# CCU_Sheet.net
KiCad netlist of a schematic drawn in Altium Designer
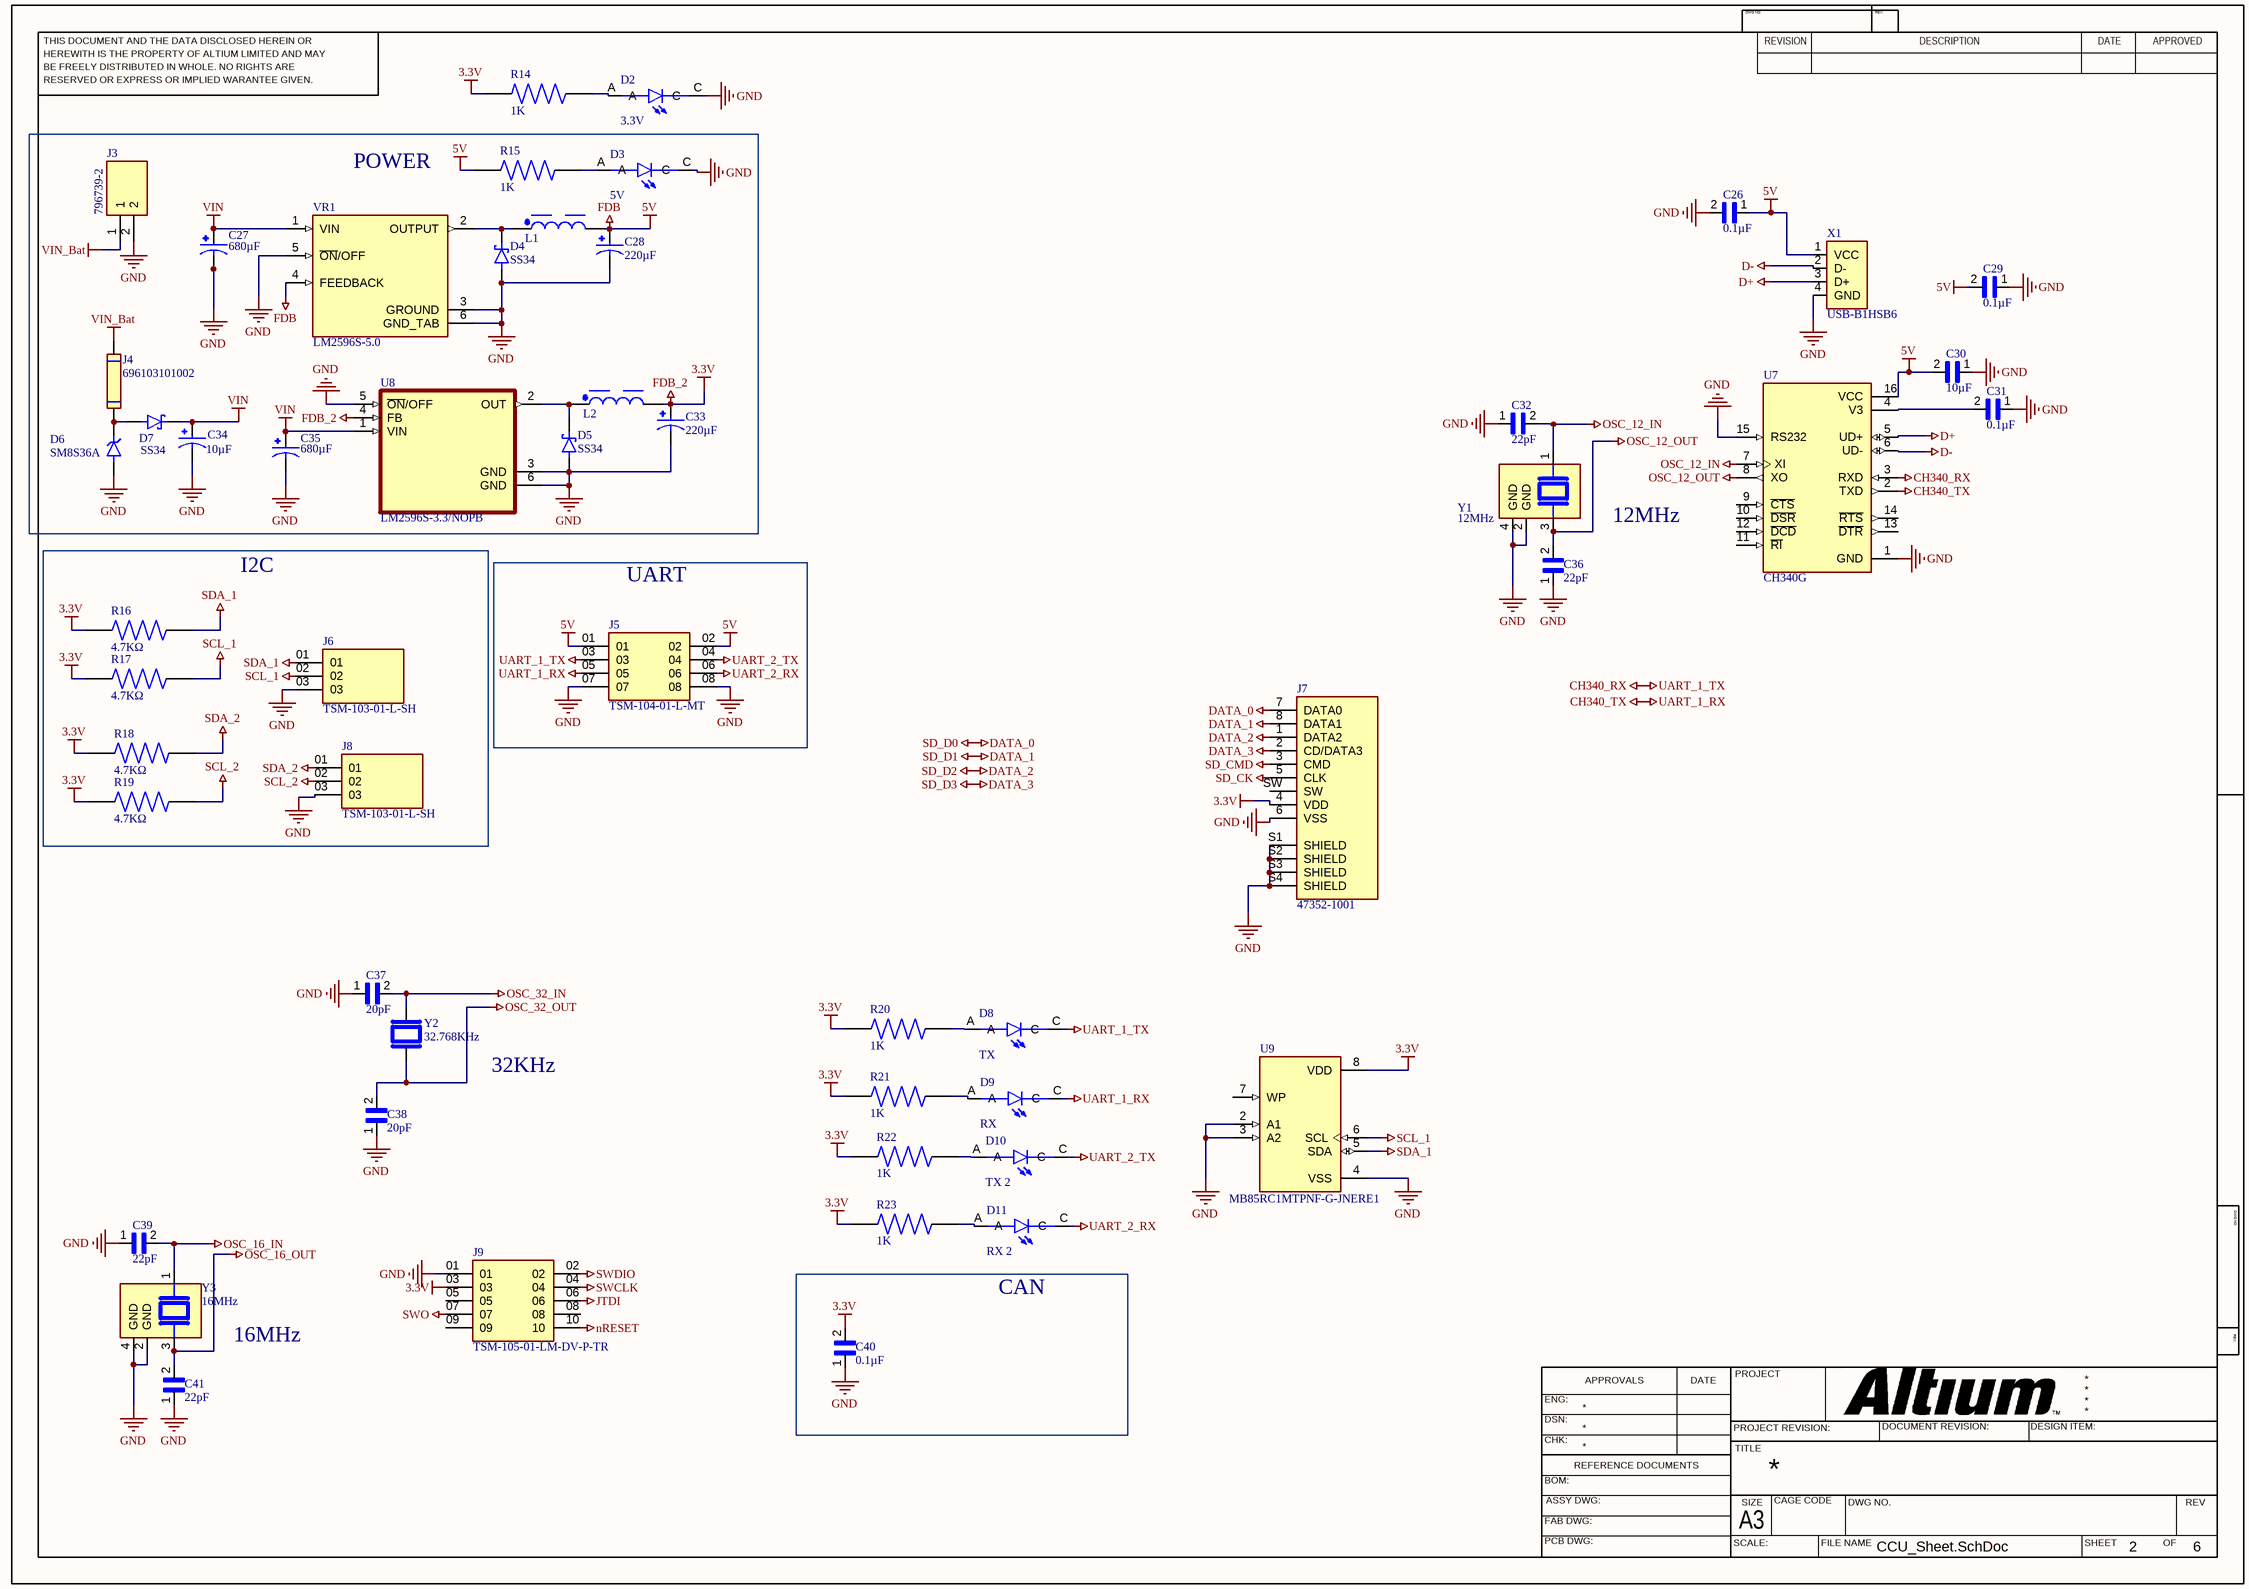
[diagram p0: CCU_Sheet.SchDoc]

(export (version "E")
  (design (tool "Eeschema 10.0.6"))
  (components
    (comp (ref "C26")
      (value "0.1µF")
      (footprint "CAPC1608X90N")
      (description "Multilayer Ceramic Capacitors MLCC - SMD/SMT")
      (fields (field (name "MP") "06035C104MAZ2A"))
      (libsource (lib "06035C104MAZ2A") (part "06035C104MAZ2A"))
    )
    (comp (ref "C27")
      (value "680µF")
      (footprint "CAP_EEEFN1E681UV")
      (description "CAP ALUM 680UF 20% 25V SMD")
      (fields (field (name "MF") "Panasonic Electronic Components") (field (name "MP") "EEE-FN1E681UV"))
      (libsource (lib "EEEFN1E681UV") (part "EEEFN1E681UV"))
    )
    (comp (ref "C28")
      (value "220µF")
      (footprint "CAP_EEEFP1V221AV")
      (description "CAP ALUM 220UF 20% 35V SMD")
      (fields (field (name "MF") "Panasonic Electronic Components") (field (name "MP") "EEE-FP1V221AV"))
      (libsource (lib "") (part "EEEFP1V221AV_1"))
    )
    (comp (ref "C29")
      (value "0.1µF")
      (footprint "CAPC1608X90N")
      (description "Multilayer Ceramic Capacitors MLCC - SMD/SMT")
      (fields (field (name "MP") "06035C104MAZ2A"))
      (libsource (lib "06035C104MAZ2A") (part "06035C104MAZ2A"))
    )
    (comp (ref "C30")
      (value "10µF")
      (footprint "CAPC1608X90N")
      (description "Multilayer Ceramic Capacitors MLCC - SMD/SMT")
      (fields (field (name "MP") "06035C104MAZ2A"))
      (libsource (lib "06035C104MAZ2A") (part "06035C104MAZ2A"))
    )
    (comp (ref "C31")
      (value "0.1µF")
      (footprint "CAPC1608X90N")
      (description "Multilayer Ceramic Capacitors MLCC - SMD/SMT")
      (fields (field (name "MP") "06035C104MAZ2A"))
      (libsource (lib "06035C104MAZ2A") (part "06035C104MAZ2A"))
    )
    (comp (ref "C32")
      (value "22pF")
      (footprint "CAPC1005X61N")
      (fields (field (name "MP") "VJ0402D200FXAAJ"))
      (libsource (lib "VJ0402D200FXAAJ") (part "VJ0402D200FXAAJ"))
    )
    (comp (ref "C33")
      (value "220µF")
      (footprint "CAP_EEEFP1V221AV")
      (description "CAP ALUM 220UF 20% 35V SMD")
      (fields (field (name "MF") "Panasonic Electronic Components") (field (name "MP") "EEE-FP1V221AV"))
      (libsource (lib "EEEFP1V221AV") (part "EEEFP1V221AV"))
    )
    (comp (ref "C34")
      (value "10µF")
      (footprint "CAPPRD500W50D500H1100")
      (description "10ÂµF 25V Aluminum Electrolytic Capacitors Radial, Can 2000 Hrs @ 85Â°C")
      (fields (field (name "MF") "Panasonic") (field (name "MP") "ECEA1EN100UB"))
      (libsource (lib "ECEA1EN100UB") (part "ECEA1EN100UB"))
    )
    (comp (ref "C35")
      (value "680µF")
      (footprint "CAP_EEEFN1E681UV")
      (description "CAP ALUM 680UF 20% 25V SMD")
      (fields (field (name "MF") "Panasonic Electronic Components") (field (name "MP") "EEE-FN1E681UV"))
      (libsource (lib "") (part "EEEFN1E681UV_1"))
    )
    (comp (ref "C36")
      (value "22pF")
      (footprint "CAPC1005X61N")
      (fields (field (name "MP") "VJ0402D200FXAAJ"))
      (libsource (lib "") (part "VJ0402D200FXAAJ_1"))
    )
    (comp (ref "C37")
      (value "20pF")
      (footprint "CAPC1005X61N")
      (fields (field (name "MP") "VJ0402D200FXAAJ"))
      (libsource (lib "VJ0402D200FXAAJ") (part "VJ0402D200FXAAJ"))
    )
    (comp (ref "C38")
      (value "20pF")
      (footprint "CAPC1005X61N")
      (fields (field (name "MP") "VJ0402D200FXAAJ"))
      (libsource (lib "") (part "VJ0402D200FXAAJ_1"))
    )
    (comp (ref "C39")
      (value "22pF")
      (footprint "CAPC1005X61N")
      (fields (field (name "MP") "VJ0402D200FXAAJ"))
      (libsource (lib "VJ0402D200FXAAJ") (part "VJ0402D200FXAAJ"))
    )
    (comp (ref "C40")
      (value "0.1µF")
      (footprint "CAPC1608X90N")
      (description "Multilayer Ceramic Capacitors MLCC - SMD/SMT")
      (fields (field (name "MP") "06035C104MAZ2A"))
      (libsource (lib "") (part "06035C104MAZ2A_1"))
    )
    (comp (ref "C41")
      (value "22pF")
      (footprint "CAPC1005X61N")
      (fields (field (name "MP") "VJ0402D200FXAAJ"))
      (libsource (lib "") (part "VJ0402D200FXAAJ_1"))
    )
    (comp (ref "D2")
      (value "3.3V")
      (footprint "LEDC2012X70N")
      (description "LED Uni-Color Green 4-Pin Chip 0805 T/R")
      (fields (field (name "MP") "597-3305-607F"))
      (libsource (lib "597-3305-607F") (part "597-3305-607F"))
    )
    (comp (ref "D3")
      (value "5V")
      (footprint "LEDC2012X70N")
      (description "LED Uni-Color Green 4-Pin Chip 0805 T/R")
      (fields (field (name "MP") "597-3305-607F"))
      (libsource (lib "597-3305-607F") (part "597-3305-607F"))
    )
    (comp (ref "D4")
      (value "SS34")
      (footprint "DIO_SS34")
      (description "3A, 40V, Schottky Rectifier")
      (fields (field (name "MF") "Taiwan Semiconductor"))
      (libsource (lib "SS34") (part "SS34"))
    )
    (comp (ref "D5")
      (value "SS34")
      (footprint "DIO_SS34")
      (description "3A, 40V, Schottky Rectifier")
      (fields (field (name "MF") "Taiwan Semiconductor"))
      (libsource (lib "SS34") (part "SS34"))
    )
    (comp (ref "D6")
      (value "SM8S36A")
      (footprint "TVSP_SM8S36A")
      (libsource (lib "SM8S36A") (part "SM8S36A"))
    )
    (comp (ref "D7")
      (value "SS34")
      (footprint "DIO_SS34")
      (description "3A, 40V, Schottky Rectifier")
      (fields (field (name "MF") "Taiwan Semiconductor"))
      (libsource (lib "SS34") (part "SS34"))
    )
    (comp (ref "D8")
      (value "TX")
      (footprint "LEDC2012X70N")
      (description "LED Uni-Color Green 4-Pin Chip 0805 T/R")
      (fields (field (name "MP") "597-3305-607F"))
      (libsource (lib "597-3305-607F") (part "597-3305-607F"))
    )
    (comp (ref "D9")
      (value "RX")
      (footprint "LEDC2012X70N")
      (description "LED Uni-Color Green 4-Pin Chip 0805 T/R")
      (fields (field (name "MP") "597-3305-607F"))
      (libsource (lib "597-3305-607F") (part "597-3305-607F"))
    )
    (comp (ref "D10")
      (value "TX 2")
      (footprint "LEDC2012X70N")
      (description "LED Uni-Color Green 4-Pin Chip 0805 T/R")
      (fields (field (name "MP") "597-3305-607F"))
      (libsource (lib "597-3305-607F") (part "597-3305-607F"))
    )
    (comp (ref "D11")
      (value "RX 2")
      (footprint "LEDC2012X70N")
      (description "LED Uni-Color Green 4-Pin Chip 0805 T/R")
      (fields (field (name "MP") "597-3305-607F"))
      (libsource (lib "597-3305-607F") (part "597-3305-607F"))
    )
    (comp (ref "J3")
      (value "796739-2")
      (footprint "TE_796739-2")
      (description "Conn Terminal Block F 2 POS 9.53mm Solder RA Thru-Hole 32A/Contact")
      (fields (field (name "MF") "TE Connectivity"))
      (libsource (lib "796739-2") (part "796739-2"))
    )
    (comp (ref "J4")
      (value "696103101002")
      (footprint "696103101002")
      (fields (field (name "MF") "{'manufacturer': u'~{W}xfcrth Elektronik'}"))
      (libsource (lib "696103101002") (part "696103101002"))
    )
    (comp (ref "J5")
      (value "TSM-104-01-L-MT")
      (footprint "SAMTEC_TSM-104-01-L-MT")
      (description "TSM Series .100 Surface Mount Terminal Strip")
      (fields (field (name "MF") "Samtec"))
      (libsource (lib "TSM-104-01-L-MT") (part "TSM-104-01-L-MT"))
    )
    (comp (ref "J6")
      (value "TSM-103-01-L-SH")
      (footprint "SAMTEC_TSM-103-01-L-SH")
      (fields (field (name "MF") "Samtec Inc."))
      (libsource (lib "TSM-103-01-L-SH (1)") (part "TSM-103-01-L-SH"))
    )
    (comp (ref "J7")
      (value "47352-1001")
      (footprint "MOLEX_47352-1001")
      (description "8 (6 + 2) Position Card Connector Secure Digital - microSDâ„¢ Surface Mount, Right Angle Gold")
      (fields (field (name "MP") "473521001") (field (name "MF") "Molex"))
      (libsource (lib "47352-1001") (part "47352-1001"))
    )
    (comp (ref "J8")
      (value "TSM-103-01-L-SH")
      (footprint "SAMTEC_TSM-103-01-L-SH")
      (fields (field (name "MF") "Samtec Inc."))
      (libsource (lib "TSM-103-01-L-SH (1)") (part "TSM-103-01-L-SH"))
    )
    (comp (ref "J9")
      (value "TSM-105-01-LM-DV-P-TR")
      (footprint "SAMTEC_TSM-105-01-LM-DV-P-TR")
      (description "TSM - Samtec 2.54mm Dual Row Vertical Surface Mount Header 5.84mm Post Height (01) - Fast Stock")
      (fields (field (name "MF") "Samtec"))
      (libsource (lib "TSM-105-01-LM-DV-P-TR") (part "TSM-105-01-LM-DV-P-TR"))
    )
    (comp (ref "L1")
      (value "33uH, 4.2A")
      (footprint "WE-PD_1210")
      (description "WE-PD SMT Power Inductor, size 1210, 33uH, 4.2A, 45mOhm")
      (fields
        (field (name "MANUFACTURER PART NUMBER") "7447709330")
        (field (name "MANUFACTURER") "Wurth Elektronik")
      )
      (libsource (lib "Altium_WE-PD_rev22g") (part "7447709330"))
    )
    (comp (ref "L2")
      (value "33uH, 4.2A")
      (footprint "WE-PD_1210")
      (description "WE-PD SMT Power Inductor, size 1210, 33uH, 4.2A, 45mOhm")
      (fields
        (field (name "MANUFACTURER PART NUMBER") "7447709330")
        (field (name "MANUFACTURER") "Wurth Elektronik")
      )
      (libsource (lib "Altium_WE-PD_rev22g") (part "7447709330"))
    )
    (comp (ref "R14")
      (value "1K")
      (footprint "RESC3116X65N")
      (fields (field (name "MF") "Yageo Corporation") (field (name "MP") "RC1206JR071KL"))
      (libsource (lib "RC1206JR-071KL") (part "RC1206JR-071KL"))
    )
    (comp (ref "R15")
      (value "1K")
      (footprint "RESC3116X65N")
      (fields (field (name "MF") "Yageo Corporation") (field (name "MP") "RC1206JR071KL"))
      (libsource (lib "RC1206JR-071KL") (part "RC1206JR-071KL"))
    )
    (comp (ref "R16")
      (value "4.7KΩ")
      (footprint "RES_ERJS06J472V")
      (fields (field (name "MP") "ERJS06J472V"))
      (libsource (lib "ERJS06J472V") (part "ERJS06J472V"))
    )
    (comp (ref "R17")
      (value "4.7KΩ")
      (footprint "RES_ERJS06J472V")
      (fields (field (name "MP") "ERJS06J472V"))
      (libsource (lib "ERJS06J472V") (part "ERJS06J472V"))
    )
    (comp (ref "R18")
      (value "4.7KΩ")
      (footprint "RES_ERJS06J472V")
      (fields (field (name "MP") "ERJS06J472V"))
      (libsource (lib "ERJS06J472V") (part "ERJS06J472V"))
    )
    (comp (ref "R19")
      (value "4.7KΩ")
      (footprint "RES_ERJS06J472V")
      (fields (field (name "MP") "ERJS06J472V"))
      (libsource (lib "ERJS06J472V") (part "ERJS06J472V"))
    )
    (comp (ref "R20")
      (value "1K")
      (footprint "RESC3116X65N")
      (fields (field (name "MF") "Yageo Corporation") (field (name "MP") "RC1206JR071KL"))
      (libsource (lib "RC1206JR-071KL") (part "RC1206JR-071KL"))
    )
    (comp (ref "R21")
      (value "1K")
      (footprint "RESC3116X65N")
      (fields (field (name "MF") "Yageo Corporation") (field (name "MP") "RC1206JR071KL"))
      (libsource (lib "RC1206JR-071KL") (part "RC1206JR-071KL"))
    )
    (comp (ref "R22")
      (value "1K")
      (footprint "RESC3116X65N")
      (fields (field (name "MF") "Yageo Corporation") (field (name "MP") "RC1206JR071KL"))
      (libsource (lib "RC1206JR-071KL") (part "RC1206JR-071KL"))
    )
    (comp (ref "R23")
      (value "1K")
      (footprint "RESC3116X65N")
      (fields (field (name "MF") "Yageo Corporation") (field (name "MP") "RC1206JR071KL"))
      (libsource (lib "RC1206JR-071KL") (part "RC1206JR-071KL"))
    )
    (comp (ref "U7")
      (value "CH340G")
      (footprint "SOIC127P600X180-16N")
      (description "USB Interface Integrated Circuit")
      (fields (field (name "MP") "Ch340G") (field (name "MF") "WCH"))
      (libsource (lib "CH340G") (part "CH340G"))
    )
    (comp (ref "U8")
      (value "LM2596S-3.3/NOPB")
      (footprint "VREG_LM2596S-3.3/NOPB")
      (libsource (lib "LM2596S-3.3_NOPB") (part "LM2596S-3.3/NOPB"))
    )
    (comp (ref "U9")
      (value "MB85RC1MTPNF-G-JNERE1")
      (footprint "SOIC127P600X175-8N")
      (description "FRAM _Ferroelectric RAM_ Memory IC 1Mb _128K x 8_ IÂ²C 3.4MHz 130ns 8-SOP")
      (fields (field (name "MF") "Fujitsu Electronics"))
      (libsource (lib "MB85RC1MTPNF-G-JNERE1") (part "MB85RC1MTPNF-G-JNERE1"))
    )
    (comp (ref "VR1")
      (value "LM2596S-5.0")
      (footprint "TO170P1524X483-6N")
      (description "SIMPLE SWITCHER&reg; 4.5V to 40V, 3A Low Component Count Step-Down Regulator")
      (fields (field (name "MP") "LM2596S-5.0/NOPB") (field (name "MF") "Texas Instruments"))
      (libsource (lib "LM2596S-5.0") (part "LM2596S-5.0"))
    )
    (comp (ref "X1")
      (value "USB-B1HSB6")
      (footprint "OST_USB-B1HSB6")
      (description "USB-B (USB TYPE-B) - Receptacle Connector 4 Position Through Hole, Right Angle")
      (fields (field (name "MF") "On Shore"))
      (libsource (lib "USB-B1HSB6") (part "USB-B1HSB6"))
    )
    (comp (ref "Y1")
      (value "12MHz")
      (footprint "XTAL_7M25090002")
      (description "16 MHz Â±10ppm Crystal 18pF 4-SMD, No Lead")
      (fields (field (name "MF") "TXC") (field (name "MP") "7M25090002"))
      (libsource (lib "7M25090002") (part "7M25090002"))
    )
    (comp (ref "Y2")
      (value "32.768KHz")
      (footprint "XTAL_ABS06-32.768KHZ-9-1-T")
      (description "32.768 kHz Â±10ppm Crystal 9pF 90 kOhms 2-SMD, No Lead")
      (fields (field (name "MF") "Abracon") (field (name "MP") "ABS06-32.768KHZ-9-1-T"))
      (libsource (lib "ABS06-32.768KHZ-9-1-T") (part "ABS06-32.768KHZ-9-1-T"))
    )
    (comp (ref "Y3")
      (value "16MHz")
      (footprint "XTAL_7M25090002")
      (description "25 MHz Â±10ppm Crystal 18pF 4-SMD, No Lead")
      (fields (field (name "MF") "TXC") (field (name "MP") "7M25090002"))
      (libsource (lib "7M25090002") (part "7M25090002"))
    )
  )
  (nets
    (net (code "1") (name "3.3V") (class "Default")
      (node (ref "C33") (pin "1") (pinfunction "1_1") (pintype "passive"))
      (node (ref "C40") (pin "2") (pinfunction "2_2") (pintype "passive"))
      (node (ref "J7") (pin "4") (pinfunction "VDD_4") (pintype "passive"))
      (node (ref "J9") (pin "03") (pinfunction "03_03") (pintype "passive"))
      (node (ref "L2") (pin "2") (pinfunction "2_2") (pintype "passive"))
      (node (ref "R14") (pin "1") (pinfunction "1_1") (pintype "passive"))
      (node (ref "R16") (pin "2") (pinfunction "2_2") (pintype "passive"))
      (node (ref "R17") (pin "1") (pinfunction "1_1") (pintype "passive"))
      (node (ref "R18") (pin "2") (pinfunction "2_2") (pintype "passive"))
      (node (ref "R19") (pin "1") (pinfunction "1_1") (pintype "passive"))
      (node (ref "R20") (pin "1") (pinfunction "1_1") (pintype "passive"))
      (node (ref "R21") (pin "1") (pinfunction "1_1") (pintype "passive"))
      (node (ref "R22") (pin "1") (pinfunction "1_1") (pintype "passive"))
      (node (ref "R23") (pin "1") (pinfunction "1_1") (pintype "passive"))
      (node (ref "U8") (pin "4") (pinfunction "FB_4") (pintype "input"))
      (node (ref "U9") (pin "8") (pinfunction "VDD_8") (pintype "power_in"))
    )
    (net (code "2") (name "5V") (class "Default")
      (node (ref "C26") (pin "1") (pinfunction "1_1") (pintype "passive"))
      (node (ref "C28") (pin "1") (pinfunction "1_1") (pintype "passive"))
      (node (ref "C29") (pin "2") (pinfunction "2_2") (pintype "passive"))
      (node (ref "C30") (pin "2") (pinfunction "2_2") (pintype "passive"))
      (node (ref "J5") (pin "01") (pinfunction "01_01") (pintype "passive"))
      (node (ref "J5") (pin "02") (pinfunction "02_02") (pintype "passive"))
      (node (ref "L1") (pin "2") (pinfunction "2_2") (pintype "passive"))
      (node (ref "R15") (pin "1") (pinfunction "1_1") (pintype "passive"))
      (node (ref "U7") (pin "16") (pinfunction "VCC_16") (pintype "power_in"))
      (node (ref "VR1") (pin "4") (pinfunction "FEEDBACK_4") (pintype "input"))
      (node (ref "X1") (pin "1") (pinfunction "VCC_1") (pintype "power_in"))
    )
    (net (code "3") (name "CH340_RX") (class "Default")
      (node (ref "D8") (pin "C") (pinfunction "C_C") (pintype "passive"))
      (node (ref "J5") (pin "03") (pinfunction "03_03") (pintype "passive"))
      (node (ref "U7") (pin "3") (pinfunction "RXD_3") (pintype "input"))
    )
    (net (code "4") (name "CH340_TX") (class "Default")
      (node (ref "D9") (pin "C") (pinfunction "C_C") (pintype "passive"))
      (node (ref "J5") (pin "05") (pinfunction "05_05") (pintype "passive"))
      (node (ref "U7") (pin "2") (pinfunction "TXD_2") (pintype "output"))
    )
    (net (code "5") (name "D+") (class "Default")
      (node (ref "U7") (pin "5") (pinfunction "UD+_5") (pintype "bidirectional"))
      (node (ref "X1") (pin "3") (pinfunction "D+_3") (pintype "bidirectional"))
    )
    (net (code "6") (name "D-") (class "Default")
      (node (ref "U7") (pin "6") (pinfunction "UD-_6") (pintype "bidirectional"))
      (node (ref "X1") (pin "2") (pinfunction "D-_2") (pintype "bidirectional"))
    )
    (net (code "7") (name "DATA_0") (class "Default")
      (node (ref "J7") (pin "7") (pinfunction "DATA0_7") (pintype "passive"))
    )
    (net (code "8") (name "DATA_1") (class "Default")
      (node (ref "J7") (pin "8") (pinfunction "DATA1_8") (pintype "passive"))
    )
    (net (code "9") (name "DATA_2") (class "Default")
      (node (ref "J7") (pin "1") (pinfunction "DATA2_1") (pintype "passive"))
    )
    (net (code "10") (name "DATA_3") (class "Default")
      (node (ref "J7") (pin "2") (pinfunction "CD/DATA3_2") (pintype "passive"))
    )
    (net (code "11") (name "GND") (class "Default")
      (node (ref "C26") (pin "2") (pinfunction "2_2") (pintype "passive"))
      (node (ref "C27") (pin "2") (pinfunction "2_2") (pintype "passive"))
      (node (ref "C28") (pin "2") (pinfunction "2_2") (pintype "passive"))
      (node (ref "C29") (pin "1") (pinfunction "1_1") (pintype "passive"))
      (node (ref "C30") (pin "1") (pinfunction "1_1") (pintype "passive"))
      (node (ref "C31") (pin "1") (pinfunction "1_1") (pintype "passive"))
      (node (ref "C32") (pin "1") (pinfunction "1_1") (pintype "passive"))
      (node (ref "C33") (pin "2") (pinfunction "2_2") (pintype "passive"))
      (node (ref "C34") (pin "N") (pinfunction "N_N") (pintype "passive"))
      (node (ref "C35") (pin "2") (pinfunction "2_2") (pintype "passive"))
      (node (ref "C36") (pin "1") (pinfunction "1_1") (pintype "passive"))
      (node (ref "C37") (pin "1") (pinfunction "1_1") (pintype "passive"))
      (node (ref "C38") (pin "1") (pinfunction "1_1") (pintype "passive"))
      (node (ref "C39") (pin "1") (pinfunction "1_1") (pintype "passive"))
      (node (ref "C40") (pin "1") (pinfunction "1_1") (pintype "passive"))
      (node (ref "C41") (pin "1") (pinfunction "1_1") (pintype "passive"))
      (node (ref "D2") (pin "C") (pinfunction "C_C") (pintype "passive"))
      (node (ref "D3") (pin "C") (pinfunction "C_C") (pintype "passive"))
      (node (ref "D4") (pin "A") (pinfunction "A_A") (pintype "passive"))
      (node (ref "D5") (pin "A") (pinfunction "A_A") (pintype "passive"))
      (node (ref "D6") (pin "2") (pinfunction "A_2") (pintype "passive"))
      (node (ref "J3") (pin "2") (pinfunction "2_2") (pintype "passive"))
      (node (ref "J5") (pin "07") (pinfunction "07_07") (pintype "passive"))
      (node (ref "J5") (pin "08") (pinfunction "08_08") (pintype "passive"))
      (node (ref "J6") (pin "03") (pinfunction "03_03") (pintype "passive"))
      (node (ref "J7") (pin "6") (pinfunction "VSS_6") (pintype "passive"))
      (node (ref "J7") (pin "S1") (pinfunction "SHIELD_S1") (pintype "passive"))
      (node (ref "J7") (pin "S2") (pinfunction "SHIELD_S2") (pintype "passive"))
      (node (ref "J7") (pin "S3") (pinfunction "SHIELD_S3") (pintype "passive"))
      (node (ref "J7") (pin "S4") (pinfunction "SHIELD_S4") (pintype "passive"))
      (node (ref "J8") (pin "03") (pinfunction "03_03") (pintype "passive"))
      (node (ref "J9") (pin "01") (pinfunction "01_01") (pintype "passive"))
      (node (ref "U7") (pin "1") (pinfunction "GND_1") (pintype "power_in"))
      (node (ref "U7") (pin "15") (pinfunction "RS232_15") (pintype "input"))
      (node (ref "U8") (pin "3") (pinfunction "GND_3") (pintype "power_in"))
      (node (ref "U8") (pin "5") (pinfunction "~{ON}/OFF_5") (pintype "input"))
      (node (ref "U8") (pin "6") (pinfunction "GND_6") (pintype "power_in"))
      (node (ref "U9") (pin "2") (pinfunction "A1_2") (pintype "input"))
      (node (ref "U9") (pin "3") (pinfunction "A2_3") (pintype "input"))
      (node (ref "U9") (pin "4") (pinfunction "VSS_4") (pintype "power_in"))
      (node (ref "VR1") (pin "3") (pinfunction "GROUND_3") (pintype "power_in"))
      (node (ref "VR1") (pin "5") (pinfunction "~{ON}/OFF_5") (pintype "input"))
      (node (ref "VR1") (pin "6") (pinfunction "GND_TAB_6") (pintype "power_in"))
      (node (ref "X1") (pin "4") (pinfunction "GND_4") (pintype "power_in"))
      (node (ref "Y1") (pin "2") (pinfunction "GND_2") (pintype "power_in"))
      (node (ref "Y1") (pin "4") (pinfunction "GND_4") (pintype "power_in"))
      (node (ref "Y3") (pin "2") (pinfunction "GND_2") (pintype "power_in"))
      (node (ref "Y3") (pin "4") (pinfunction "GND_4") (pintype "power_in"))
    )
    (net (code "12") (name "JTDI") (class "Default")
      (node (ref "J9") (pin "06") (pinfunction "06_06") (pintype "passive"))
    )
    (net (code "13") (name "Net-(D2-PadA)") (class "Default")
      (node (ref "D2") (pin "A") (pinfunction "A_A") (pintype "passive"))
      (node (ref "R14") (pin "2") (pinfunction "2_2") (pintype "passive"))
    )
    (net (code "14") (name "Net-(D3-PadA)") (class "Default")
      (node (ref "D3") (pin "A") (pinfunction "A_A") (pintype "passive"))
      (node (ref "R15") (pin "2") (pinfunction "2_2") (pintype "passive"))
    )
    (net (code "15") (name "Net-(D4-K)") (class "Default")
      (node (ref "D4") (pin "C") (pinfunction "K_C") (pintype "passive"))
      (node (ref "L1") (pin "1") (pinfunction "1_1") (pintype "passive"))
      (node (ref "VR1") (pin "2") (pinfunction "OUTPUT_2") (pintype "output"))
    )
    (net (code "16") (name "Net-(D5-K)") (class "Default")
      (node (ref "D5") (pin "C") (pinfunction "K_C") (pintype "passive"))
      (node (ref "L2") (pin "1") (pinfunction "1_1") (pintype "passive"))
      (node (ref "U8") (pin "2") (pinfunction "OUT_2") (pintype "output"))
    )
    (net (code "17") (name "Net-(D6-K)") (class "Default")
      (node (ref "D6") (pin "1") (pinfunction "K_1") (pintype "passive"))
      (node (ref "D7") (pin "A") (pinfunction "A_A") (pintype "passive"))
      (node (ref "J4") (pin "1") (pinfunction "1_1") (pintype "passive"))
    )
    (net (code "18") (name "Net-(D8-PadA)") (class "Default")
      (node (ref "D8") (pin "A") (pinfunction "A_A") (pintype "passive"))
      (node (ref "R20") (pin "2") (pinfunction "2_2") (pintype "passive"))
    )
    (net (code "19") (name "Net-(D9-PadA)") (class "Default")
      (node (ref "D9") (pin "A") (pinfunction "A_A") (pintype "passive"))
      (node (ref "R21") (pin "2") (pinfunction "2_2") (pintype "passive"))
    )
    (net (code "20") (name "Net-(D10-PadA)") (class "Default")
      (node (ref "D10") (pin "A") (pinfunction "A_A") (pintype "passive"))
      (node (ref "R22") (pin "2") (pinfunction "2_2") (pintype "passive"))
    )
    (net (code "21") (name "Net-(D11-PadA)") (class "Default")
      (node (ref "D11") (pin "A") (pinfunction "A_A") (pintype "passive"))
      (node (ref "R23") (pin "2") (pinfunction "2_2") (pintype "passive"))
    )
    (net (code "22") (name "Net-(U7-V3)") (class "Default")
      (node (ref "C31") (pin "2") (pinfunction "2_2") (pintype "passive"))
      (node (ref "U7") (pin "4") (pinfunction "V3_4") (pintype "power_in"))
    )
    (net (code "23") (name "OSC_12_IN") (class "Default")
      (node (ref "C32") (pin "2") (pinfunction "2_2") (pintype "passive"))
      (node (ref "U7") (pin "7") (pinfunction "XI_7") (pintype "input"))
      (node (ref "Y1") (pin "1") (pinfunction "1_1") (pintype "passive"))
    )
    (net (code "24") (name "OSC_12_OUT") (class "Default")
      (node (ref "C36") (pin "2") (pinfunction "2_2") (pintype "passive"))
      (node (ref "U7") (pin "8") (pinfunction "XO_8") (pintype "output"))
      (node (ref "Y1") (pin "3") (pinfunction "2_3") (pintype "passive"))
    )
    (net (code "25") (name "OSC_16_IN") (class "Default")
      (node (ref "C39") (pin "2") (pinfunction "2_2") (pintype "passive"))
      (node (ref "Y3") (pin "1") (pinfunction "1_1") (pintype "passive"))
    )
    (net (code "26") (name "OSC_16_OUT") (class "Default")
      (node (ref "C41") (pin "2") (pinfunction "2_2") (pintype "passive"))
      (node (ref "Y3") (pin "3") (pinfunction "2_3") (pintype "passive"))
    )
    (net (code "27") (name "OSC_32_IN") (class "Default")
      (node (ref "C37") (pin "2") (pinfunction "2_2") (pintype "passive"))
      (node (ref "Y2") (pin "2") (pinfunction "2_2") (pintype "passive"))
    )
    (net (code "28") (name "OSC_32_OUT") (class "Default")
      (node (ref "C38") (pin "2") (pinfunction "2_2") (pintype "passive"))
      (node (ref "Y2") (pin "1") (pinfunction "1_1") (pintype "passive"))
    )
    (net (code "29") (name "SCL_1") (class "Default")
      (node (ref "J6") (pin "02") (pinfunction "02_02") (pintype "passive"))
      (node (ref "R17") (pin "2") (pinfunction "2_2") (pintype "passive"))
      (node (ref "U9") (pin "6") (pinfunction "SCL_6") (pintype "input"))
    )
    (net (code "30") (name "SCL_2") (class "Default")
      (node (ref "J8") (pin "02") (pinfunction "02_02") (pintype "passive"))
      (node (ref "R19") (pin "2") (pinfunction "2_2") (pintype "passive"))
    )
    (net (code "31") (name "SDA_1") (class "Default")
      (node (ref "J6") (pin "01") (pinfunction "01_01") (pintype "passive"))
      (node (ref "R16") (pin "1") (pinfunction "1_1") (pintype "passive"))
      (node (ref "U9") (pin "5") (pinfunction "SDA_5") (pintype "bidirectional"))
    )
    (net (code "32") (name "SDA_2") (class "Default")
      (node (ref "J8") (pin "01") (pinfunction "01_01") (pintype "passive"))
      (node (ref "R18") (pin "1") (pinfunction "1_1") (pintype "passive"))
    )
    (net (code "33") (name "SD_CK") (class "Default")
      (node (ref "J7") (pin "5") (pinfunction "CLK_5") (pintype "passive"))
    )
    (net (code "34") (name "SD_CMD") (class "Default")
      (node (ref "J7") (pin "3") (pinfunction "CMD_3") (pintype "passive"))
    )
    (net (code "35") (name "SWCLK") (class "Default")
      (node (ref "J9") (pin "04") (pinfunction "04_04") (pintype "passive"))
    )
    (net (code "36") (name "SWDIO") (class "Default")
      (node (ref "J9") (pin "02") (pinfunction "02_02") (pintype "passive"))
    )
    (net (code "37") (name "SWO") (class "Default")
      (node (ref "J9") (pin "07") (pinfunction "07_07") (pintype "passive"))
    )
    (net (code "38") (name "UART_2_RX") (class "Default")
      (node (ref "D11") (pin "C") (pinfunction "C_C") (pintype "passive"))
      (node (ref "J5") (pin "06") (pinfunction "06_06") (pintype "passive"))
    )
    (net (code "39") (name "UART_2_TX") (class "Default")
      (node (ref "D10") (pin "C") (pinfunction "C_C") (pintype "passive"))
      (node (ref "J5") (pin "04") (pinfunction "04_04") (pintype "passive"))
    )
    (net (code "40") (name "VIN") (class "Default")
      (node (ref "C27") (pin "1") (pinfunction "1_1") (pintype "passive"))
      (node (ref "C34") (pin "P") (pinfunction "P_P") (pintype "passive"))
      (node (ref "C35") (pin "1") (pinfunction "1_1") (pintype "passive"))
      (node (ref "D7") (pin "C") (pinfunction "K_C") (pintype "passive"))
      (node (ref "U8") (pin "1") (pinfunction "VIN_1") (pintype "input"))
      (node (ref "VR1") (pin "1") (pinfunction "VIN_1") (pintype "input"))
    )
    (net (code "41") (name "VIN_Bat") (class "Default")
      (node (ref "J3") (pin "1") (pinfunction "1_1") (pintype "passive"))
      (node (ref "J4") (pin "2") (pinfunction "2_2") (pintype "passive"))
    )
    (net (code "42") (name "nRESET") (class "Default")
      (node (ref "J9") (pin "10") (pinfunction "10_10") (pintype "passive"))
    )
    (net (code "43") (name "unconnected-(J7-PadSW)") (class "Default")
      (node (ref "J7") (pin "SW") (pinfunction "SW_SW") (pintype "passive"))
    )
    (net (code "44") (name "unconnected-(J9-Pad05)") (class "Default")
      (node (ref "J9") (pin "05") (pinfunction "05_05") (pintype "passive"))
    )
    (net (code "45") (name "unconnected-(J9-Pad08)") (class "Default")
      (node (ref "J9") (pin "08") (pinfunction "08_08") (pintype "passive"))
    )
    (net (code "46") (name "unconnected-(J9-Pad09)") (class "Default")
      (node (ref "J9") (pin "09") (pinfunction "09_09") (pintype "passive"))
    )
    (net (code "47") (name "unconnected-(U7-~{CTS}-Pad9)") (class "Default")
      (node (ref "U7") (pin "9") (pinfunction "~{CTS}_9") (pintype "input"))
    )
    (net (code "48") (name "unconnected-(U7-~{DCD}-Pad12)") (class "Default")
      (node (ref "U7") (pin "12") (pinfunction "~{DCD}_12") (pintype "input"))
    )
    (net (code "49") (name "unconnected-(U7-~{DSR}-Pad10)") (class "Default")
      (node (ref "U7") (pin "10") (pinfunction "~{DSR}_10") (pintype "input"))
    )
    (net (code "50") (name "unconnected-(U7-~{DTR}-Pad13)") (class "Default")
      (node (ref "U7") (pin "13") (pinfunction "~{DTR}_13") (pintype "output"))
    )
    (net (code "51") (name "unconnected-(U7-~{RI}-Pad11)") (class "Default")
      (node (ref "U7") (pin "11") (pinfunction "~{RI}_11") (pintype "input"))
    )
    (net (code "52") (name "unconnected-(U7-~{RTS}-Pad14)") (class "Default")
      (node (ref "U7") (pin "14") (pinfunction "~{RTS}_14") (pintype "output"))
    )
    (net (code "53") (name "unconnected-(U9-WP-Pad7)") (class "Default")
      (node (ref "U9") (pin "7") (pinfunction "WP_7") (pintype "input"))
    )
  )
)
